# PCB2.net
KiCad netlist of a schematic drawn in EAGLE
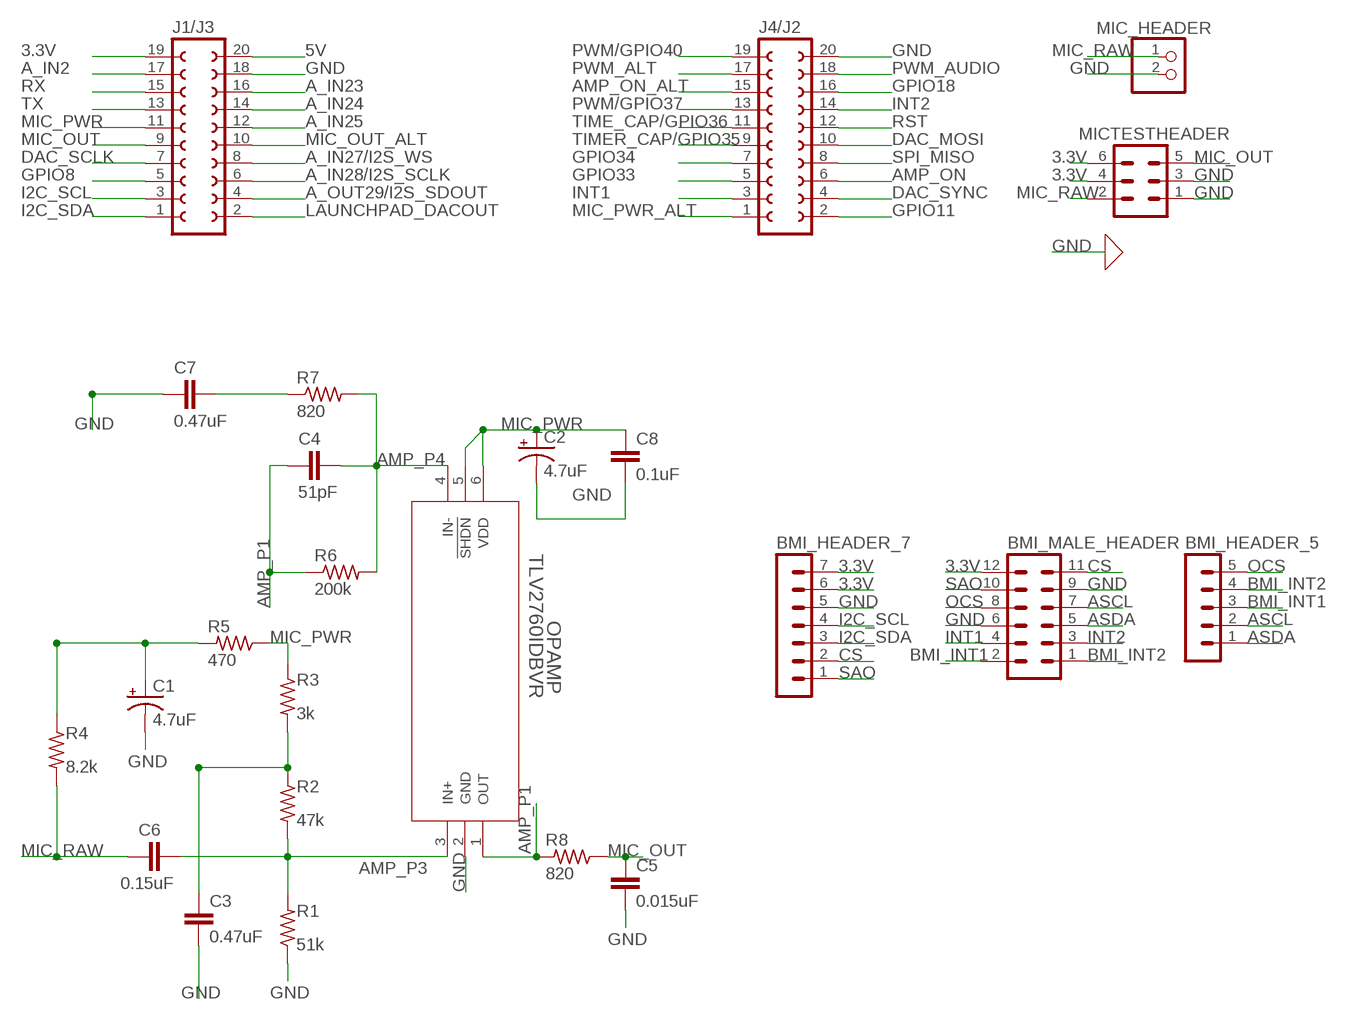
[diagram p0: schematic, sheet 1]

(export (version "E")
  (design (tool "Eeschema 10.0.6"))
  (components
    (comp (ref "BMI_HEADER_5")
      (value "MA05-1")
      (footprint "eagle-import:MA05-1")
      (libsource (lib "eagle-import") (part "MA05-1"))
    )
    (comp (ref "BMI_HEADER_7")
      (value "MA07-1")
      (footprint "eagle-import:MA07-1")
      (libsource (lib "eagle-import") (part "MA07-1"))
    )
    (comp (ref "BMI_MALE_HEADER")
      (value "MA06-2")
      (footprint "eagle-import:MA06-2")
      (libsource (lib "eagle-import") (part "MA06-2"))
    )
    (comp (ref "C1")
      (value "4.7uF")
      (footprint "eagle-import:B_3528-21W")
      (libsource (lib "eagle-import") (part "CPOL-USB/3528-21W"))
    )
    (comp (ref "C2")
      (value "4.7uF")
      (footprint "eagle-import:B_3528-21W")
      (libsource (lib "eagle-import") (part "CPOL-USB/3528-21W"))
    )
    (comp (ref "C3")
      (value "0.47uF")
      (footprint "eagle-import:C0603")
      (libsource (lib "eagle-import") (part "C-EUC0603"))
    )
    (comp (ref "C4")
      (value "51pF")
      (footprint "eagle-import:C0603")
      (libsource (lib "eagle-import") (part "C-EUC0603"))
    )
    (comp (ref "C5")
      (value "0.015uF")
      (footprint "eagle-import:C0603")
      (libsource (lib "eagle-import") (part "C-EUC0603"))
    )
    (comp (ref "C6")
      (value "0.15uF")
      (footprint "eagle-import:C0603")
      (libsource (lib "eagle-import") (part "C-EUC0603"))
    )
    (comp (ref "C7")
      (value "0.47uF")
      (footprint "eagle-import:C0603")
      (libsource (lib "eagle-import") (part "C-EUC0603"))
    )
    (comp (ref "C8")
      (value "0.1uF")
      (footprint "eagle-import:C0603")
      (libsource (lib "eagle-import") (part "C-EUC0603"))
    )
    (comp (ref "J1/J3")
      (value "FE10-2W")
      (footprint "eagle-import:FE10-2W")
      (libsource (lib "eagle-import") (part "FE10-2W"))
    )
    (comp (ref "J4/J2")
      (value "FE10-2W")
      (footprint "eagle-import:FE10-2W")
      (libsource (lib "eagle-import") (part "FE10-2W"))
    )
    (comp (ref "MICTESTHEADER")
      (value "MA03-2")
      (footprint "eagle-import:MA03-2")
      (libsource (lib "eagle-import") (part "MA03-2"))
    )
    (comp (ref "MIC_HEADER")
      (value "PINHD-1X2")
      (footprint "eagle-import:1X02")
      (libsource (lib "eagle-import") (part "PINHD-1X2"))
    )
    (comp (ref "OPAMP")
      (value "TLV2760IDBVR")
      (footprint "eagle-import:DBV6")
      (fields
        (field (name "GENERIC_PART_NUMBER") "TLV2760")
        (field (name "MANUFACTURER") "Texas Instruments")
      )
      (libsource (lib "eagle-import") (part "TLV2760IDBVR"))
    )
    (comp (ref "R1")
      (value "51k")
      (footprint "eagle-import:MINI_MELF-0204R")
      (libsource (lib "eagle-import") (part "R-US_MELF0204R"))
    )
    (comp (ref "R2")
      (value "47k")
      (footprint "eagle-import:MINI_MELF-0204R")
      (libsource (lib "eagle-import") (part "R-US_MELF0204R"))
    )
    (comp (ref "R3")
      (value "3k")
      (footprint "eagle-import:MINI_MELF-0204R")
      (libsource (lib "eagle-import") (part "R-US_MELF0204R"))
    )
    (comp (ref "R4")
      (value "8.2k")
      (footprint "eagle-import:MINI_MELF-0204R")
      (libsource (lib "eagle-import") (part "R-US_MELF0204R"))
    )
    (comp (ref "R5")
      (value "470")
      (footprint "eagle-import:MINI_MELF-0204R")
      (libsource (lib "eagle-import") (part "R-US_MELF0204R"))
    )
    (comp (ref "R6")
      (value "200k")
      (footprint "eagle-import:MINI_MELF-0204R")
      (libsource (lib "eagle-import") (part "R-US_MELF0204R"))
    )
    (comp (ref "R7")
      (value "820")
      (footprint "eagle-import:MINI_MELF-0204R")
      (libsource (lib "eagle-import") (part "R-US_MELF0204R"))
    )
    (comp (ref "R8")
      (value "820")
      (footprint "eagle-import:MINI_MELF-0204R")
      (libsource (lib "eagle-import") (part "R-US_MELF0204R"))
    )
  )
  (nets
    (net (code "1") (name "/3.3V") (class "Default")
      (node (ref "BMI_HEADER_7") (pin "6") (pinfunction "6_6") (pintype "passive"))
      (node (ref "BMI_HEADER_7") (pin "7") (pinfunction "7_7") (pintype "passive"))
      (node (ref "BMI_MALE_HEADER") (pin "12") (pinfunction "12_12") (pintype "passive"))
      (node (ref "J1/J3") (pin "19") (pinfunction "19_19") (pintype "passive"))
      (node (ref "MICTESTHEADER") (pin "4") (pinfunction "4_4") (pintype "passive"))
      (node (ref "MICTESTHEADER") (pin "6") (pinfunction "6_6") (pintype "passive"))
    )
    (net (code "2") (name "/5V") (class "Default")
      (node (ref "J1/J3") (pin "20") (pinfunction "20_20") (pintype "passive"))
    )
    (net (code "3") (name "/AMP_ON") (class "Default")
      (node (ref "J4/J2") (pin "6") (pinfunction "6_6") (pintype "passive"))
    )
    (net (code "4") (name "/AMP_ON_ALT") (class "Default")
      (node (ref "J4/J2") (pin "15") (pinfunction "15_15") (pintype "passive"))
    )
    (net (code "5") (name "/AMP_P1") (class "Default")
      (node (ref "C4") (pin "2") (pinfunction "2_2") (pintype "passive"))
      (node (ref "OPAMP") (pin "1") (pinfunction "OUT_1") (pintype "output"))
      (node (ref "R6") (pin "1") (pinfunction "1_1") (pintype "passive"))
      (node (ref "R8") (pin "2") (pinfunction "2_2") (pintype "passive"))
    )
    (net (code "6") (name "/AMP_P3") (class "Default")
      (node (ref "C6") (pin "2") (pinfunction "2_2") (pintype "passive"))
      (node (ref "OPAMP") (pin "3") (pinfunction "IN+_3") (pintype "input"))
      (node (ref "R1") (pin "2") (pinfunction "2_2") (pintype "passive"))
      (node (ref "R2") (pin "2") (pinfunction "2_2") (pintype "passive"))
    )
    (net (code "7") (name "/AMP_P4") (class "Default")
      (node (ref "C4") (pin "1") (pinfunction "1_1") (pintype "passive"))
      (node (ref "OPAMP") (pin "4") (pinfunction "IN-_4") (pintype "input"))
      (node (ref "R6") (pin "2") (pinfunction "2_2") (pintype "passive"))
      (node (ref "R7") (pin "2") (pinfunction "2_2") (pintype "passive"))
    )
    (net (code "8") (name "/ASCL") (class "Default")
      (node (ref "BMI_HEADER_5") (pin "2") (pinfunction "2_2") (pintype "passive"))
      (node (ref "BMI_MALE_HEADER") (pin "7") (pinfunction "7_7") (pintype "passive"))
    )
    (net (code "9") (name "/ASDA") (class "Default")
      (node (ref "BMI_HEADER_5") (pin "1") (pinfunction "1_1") (pintype "passive"))
      (node (ref "BMI_MALE_HEADER") (pin "5") (pinfunction "5_5") (pintype "passive"))
    )
    (net (code "10") (name "/A_IN2") (class "Default")
      (node (ref "J1/J3") (pin "17") (pinfunction "17_17") (pintype "passive"))
    )
    (net (code "11") (name "/A_IN23") (class "Default")
      (node (ref "J1/J3") (pin "16") (pinfunction "16_16") (pintype "passive"))
    )
    (net (code "12") (name "/A_IN24") (class "Default")
      (node (ref "J1/J3") (pin "14") (pinfunction "14_14") (pintype "passive"))
    )
    (net (code "13") (name "/A_IN25") (class "Default")
      (node (ref "J1/J3") (pin "12") (pinfunction "12_12") (pintype "passive"))
    )
    (net (code "14") (name "/A_IN27{slash}I2S_WS") (class "Default")
      (node (ref "J1/J3") (pin "8") (pinfunction "8_8") (pintype "passive"))
    )
    (net (code "15") (name "/A_IN28{slash}I2S_SCLK") (class "Default")
      (node (ref "J1/J3") (pin "6") (pinfunction "6_6") (pintype "passive"))
    )
    (net (code "16") (name "/A_OUT29{slash}I2S_SDOUT") (class "Default")
      (node (ref "J1/J3") (pin "4") (pinfunction "4_4") (pintype "passive"))
    )
    (net (code "17") (name "/BMI_INT1") (class "Default")
      (node (ref "BMI_HEADER_5") (pin "3") (pinfunction "3_3") (pintype "passive"))
      (node (ref "BMI_MALE_HEADER") (pin "2") (pinfunction "2_2") (pintype "passive"))
    )
    (net (code "18") (name "/BMI_INT2") (class "Default")
      (node (ref "BMI_HEADER_5") (pin "4") (pinfunction "4_4") (pintype "passive"))
      (node (ref "BMI_MALE_HEADER") (pin "1") (pinfunction "1_1") (pintype "passive"))
    )
    (net (code "19") (name "/CS") (class "Default")
      (node (ref "BMI_HEADER_7") (pin "2") (pinfunction "2_2") (pintype "passive"))
      (node (ref "BMI_MALE_HEADER") (pin "11") (pinfunction "11_11") (pintype "passive"))
    )
    (net (code "20") (name "/DAC_MOSI") (class "Default")
      (node (ref "J4/J2") (pin "10") (pinfunction "10_10") (pintype "passive"))
    )
    (net (code "21") (name "/DAC_SCLK") (class "Default")
      (node (ref "J1/J3") (pin "7") (pinfunction "7_7") (pintype "passive"))
    )
    (net (code "22") (name "/DAC_SYNC") (class "Default")
      (node (ref "J4/J2") (pin "4") (pinfunction "4_4") (pintype "passive"))
    )
    (net (code "23") (name "/GPIO8") (class "Default")
      (node (ref "J1/J3") (pin "5") (pinfunction "5_5") (pintype "passive"))
    )
    (net (code "24") (name "/GPIO11") (class "Default")
      (node (ref "J4/J2") (pin "2") (pinfunction "2_2") (pintype "passive"))
    )
    (net (code "25") (name "/GPIO18") (class "Default")
      (node (ref "J4/J2") (pin "16") (pinfunction "16_16") (pintype "passive"))
    )
    (net (code "26") (name "/GPIO33") (class "Default")
      (node (ref "J4/J2") (pin "5") (pinfunction "5_5") (pintype "passive"))
    )
    (net (code "27") (name "/GPIO34") (class "Default")
      (node (ref "J4/J2") (pin "7") (pinfunction "7_7") (pintype "passive"))
    )
    (net (code "28") (name "/I2C_SCL") (class "Default")
      (node (ref "BMI_HEADER_7") (pin "4") (pinfunction "4_4") (pintype "passive"))
      (node (ref "J1/J3") (pin "3") (pinfunction "3_3") (pintype "passive"))
    )
    (net (code "29") (name "/I2C_SDA") (class "Default")
      (node (ref "BMI_HEADER_7") (pin "3") (pinfunction "3_3") (pintype "passive"))
      (node (ref "J1/J3") (pin "1") (pinfunction "1_1") (pintype "passive"))
    )
    (net (code "30") (name "/INT1") (class "Default")
      (node (ref "BMI_MALE_HEADER") (pin "4") (pinfunction "4_4") (pintype "passive"))
      (node (ref "J4/J2") (pin "3") (pinfunction "3_3") (pintype "passive"))
    )
    (net (code "31") (name "/INT2") (class "Default")
      (node (ref "BMI_MALE_HEADER") (pin "3") (pinfunction "3_3") (pintype "passive"))
      (node (ref "J4/J2") (pin "14") (pinfunction "14_14") (pintype "passive"))
    )
    (net (code "32") (name "/LAUNCHPAD_DACOUT") (class "Default")
      (node (ref "J1/J3") (pin "2") (pinfunction "2_2") (pintype "passive"))
    )
    (net (code "33") (name "/MIC_OUT") (class "Default")
      (node (ref "C5") (pin "1") (pinfunction "1_1") (pintype "passive"))
      (node (ref "J1/J3") (pin "9") (pinfunction "9_9") (pintype "passive"))
      (node (ref "MICTESTHEADER") (pin "5") (pinfunction "5_5") (pintype "passive"))
      (node (ref "R8") (pin "1") (pinfunction "1_1") (pintype "passive"))
    )
    (net (code "34") (name "/MIC_OUT_ALT") (class "Default")
      (node (ref "J1/J3") (pin "10") (pinfunction "10_10") (pintype "passive"))
    )
    (net (code "35") (name "/MIC_PWR") (class "Default")
      (node (ref "C2") (pin "+") (pinfunction "+_+") (pintype "passive"))
      (node (ref "C8") (pin "1") (pinfunction "1_1") (pintype "passive"))
      (node (ref "J1/J3") (pin "11") (pinfunction "11_11") (pintype "passive"))
      (node (ref "OPAMP") (pin "5") (pinfunction "~{SHDN}_5") (pintype "passive"))
      (node (ref "OPAMP") (pin "6") (pinfunction "VDD_6") (pintype "power_in"))
      (node (ref "R3") (pin "1") (pinfunction "1_1") (pintype "passive"))
      (node (ref "R5") (pin "1") (pinfunction "1_1") (pintype "passive"))
    )
    (net (code "36") (name "/MIC_PWR_ALT") (class "Default")
      (node (ref "J4/J2") (pin "1") (pinfunction "1_1") (pintype "passive"))
    )
    (net (code "37") (name "/MIC_RAW") (class "Default")
      (node (ref "C6") (pin "1") (pinfunction "1_1") (pintype "passive"))
      (node (ref "MICTESTHEADER") (pin "2") (pinfunction "2_2") (pintype "passive"))
      (node (ref "MIC_HEADER") (pin "1") (pinfunction "1_1") (pintype "passive"))
      (node (ref "R4") (pin "2") (pinfunction "2_2") (pintype "passive"))
    )
    (net (code "38") (name "/OCS") (class "Default")
      (node (ref "BMI_HEADER_5") (pin "5") (pinfunction "5_5") (pintype "passive"))
      (node (ref "BMI_MALE_HEADER") (pin "8") (pinfunction "8_8") (pintype "passive"))
    )
    (net (code "39") (name "/PWM_ALT") (class "Default")
      (node (ref "J4/J2") (pin "17") (pinfunction "17_17") (pintype "passive"))
    )
    (net (code "40") (name "/PWM_AUDIO") (class "Default")
      (node (ref "J4/J2") (pin "18") (pinfunction "18_18") (pintype "passive"))
    )
    (net (code "41") (name "/PWM{slash}GPIO37") (class "Default")
      (node (ref "J4/J2") (pin "13") (pinfunction "13_13") (pintype "passive"))
    )
    (net (code "42") (name "/PWM{slash}GPIO40") (class "Default")
      (node (ref "J4/J2") (pin "19") (pinfunction "19_19") (pintype "passive"))
    )
    (net (code "43") (name "/RST") (class "Default")
      (node (ref "J4/J2") (pin "12") (pinfunction "12_12") (pintype "passive"))
    )
    (net (code "44") (name "/RX") (class "Default")
      (node (ref "J1/J3") (pin "15") (pinfunction "15_15") (pintype "passive"))
    )
    (net (code "45") (name "/SAO") (class "Default")
      (node (ref "BMI_HEADER_7") (pin "1") (pinfunction "1_1") (pintype "passive"))
      (node (ref "BMI_MALE_HEADER") (pin "10") (pinfunction "10_10") (pintype "passive"))
    )
    (net (code "46") (name "/SPI_MISO") (class "Default")
      (node (ref "J4/J2") (pin "8") (pinfunction "8_8") (pintype "passive"))
    )
    (net (code "47") (name "/TIMER_CAP{slash}GPIO35") (class "Default")
      (node (ref "J4/J2") (pin "9") (pinfunction "9_9") (pintype "passive"))
    )
    (net (code "48") (name "/TIME_CAP{slash}GPIO36") (class "Default")
      (node (ref "J4/J2") (pin "11") (pinfunction "11_11") (pintype "passive"))
    )
    (net (code "49") (name "/TX") (class "Default")
      (node (ref "J1/J3") (pin "13") (pinfunction "13_13") (pintype "passive"))
    )
    (net (code "50") (name "GND") (class "Default")
      (node (ref "BMI_HEADER_7") (pin "5") (pinfunction "5_5") (pintype "passive"))
      (node (ref "BMI_MALE_HEADER") (pin "6") (pinfunction "6_6") (pintype "passive"))
      (node (ref "BMI_MALE_HEADER") (pin "9") (pinfunction "9_9") (pintype "passive"))
      (node (ref "C1") (pin "-") (pinfunction "-_-") (pintype "passive"))
      (node (ref "C2") (pin "-") (pinfunction "-_-") (pintype "passive"))
      (node (ref "C3") (pin "2") (pinfunction "2_2") (pintype "passive"))
      (node (ref "C5") (pin "2") (pinfunction "2_2") (pintype "passive"))
      (node (ref "C7") (pin "2") (pinfunction "2_2") (pintype "passive"))
      (node (ref "C8") (pin "2") (pinfunction "2_2") (pintype "passive"))
      (node (ref "J1/J3") (pin "18") (pinfunction "18_18") (pintype "passive"))
      (node (ref "J4/J2") (pin "20") (pinfunction "20_20") (pintype "passive"))
      (node (ref "MICTESTHEADER") (pin "1") (pinfunction "1_1") (pintype "passive"))
      (node (ref "MICTESTHEADER") (pin "3") (pinfunction "3_3") (pintype "passive"))
      (node (ref "MIC_HEADER") (pin "2") (pinfunction "2_2") (pintype "passive"))
      (node (ref "OPAMP") (pin "2") (pinfunction "GND_2") (pintype "power_in"))
      (node (ref "R1") (pin "1") (pinfunction "1_1") (pintype "passive"))
    )
    (net (code "51") (name "Net-(C1-Pad+)") (class "Default")
      (node (ref "C1") (pin "+") (pinfunction "+_+") (pintype "passive"))
      (node (ref "R4") (pin "1") (pinfunction "1_1") (pintype "passive"))
      (node (ref "R5") (pin "2") (pinfunction "2_2") (pintype "passive"))
    )
    (net (code "52") (name "Net-(C3-Pad1)") (class "Default")
      (node (ref "C3") (pin "1") (pinfunction "1_1") (pintype "passive"))
      (node (ref "R2") (pin "1") (pinfunction "1_1") (pintype "passive"))
      (node (ref "R3") (pin "2") (pinfunction "2_2") (pintype "passive"))
    )
    (net (code "53") (name "Net-(C7-Pad1)") (class "Default")
      (node (ref "C7") (pin "1") (pinfunction "1_1") (pintype "passive"))
      (node (ref "R7") (pin "1") (pinfunction "1_1") (pintype "passive"))
    )
  )
)
